# ascii.net
KiCad netlist of a schematic drawn in Altium Designer
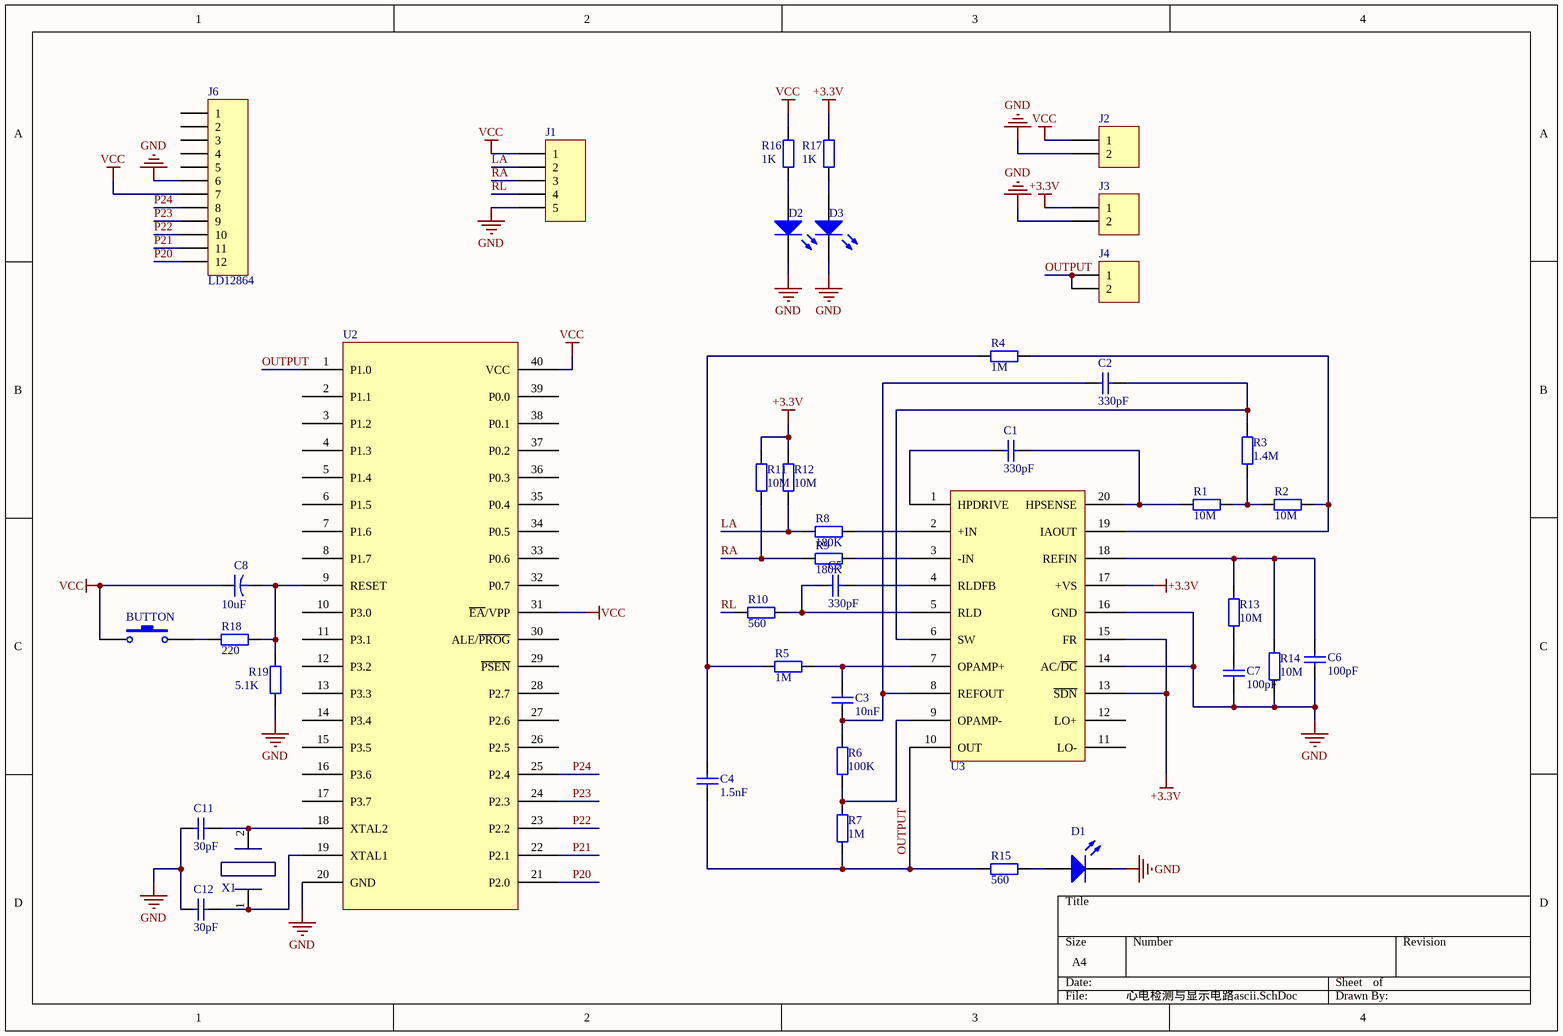
[diagram p0: 心电检测与显示电路ascii.SchDoc]

(export (version "E")
  (design (tool "Eeschema 10.0.6"))
  (components
    (comp (ref "BUTTON")
      (value "SW-PB")
      (footprint "SPST-2")
      (description "Switch")
      (fields (field (name "PUBLISHER") "Altium Limited"))
      (libsource (lib "Miscellaneous Devices") (part "SW-PB"))
    )
    (comp (ref "C1")
      (value "330pF")
      (footprint "RAD-0.3")
      (description "Capacitor")
      (fields (field (name "Comment") "Cap") (field (name "PUBLISHER") "Altium Limited"))
      (libsource (lib "Miscellaneous Devices") (part "Cap"))
    )
    (comp (ref "C2")
      (value "330pF")
      (footprint "RAD-0.3")
      (description "Capacitor")
      (fields (field (name "Comment") "Cap") (field (name "PUBLISHER") "Altium Limited"))
      (libsource (lib "Miscellaneous Devices") (part "Cap"))
    )
    (comp (ref "C3")
      (value "10nF")
      (footprint "RAD-0.3")
      (description "Capacitor")
      (fields (field (name "Comment") "Cap") (field (name "PUBLISHER") "Altium Limited"))
      (libsource (lib "Miscellaneous Devices") (part "Cap"))
    )
    (comp (ref "C4")
      (value "1.5nF")
      (footprint "RAD-0.3")
      (description "Capacitor")
      (fields (field (name "Comment") "Cap") (field (name "PUBLISHER") "Altium Limited"))
      (libsource (lib "Miscellaneous Devices") (part "Cap"))
    )
    (comp (ref "C5")
      (value "330pF")
      (footprint "RAD-0.3")
      (description "Capacitor")
      (fields (field (name "Comment") "Cap") (field (name "PUBLISHER") "Altium Limited"))
      (libsource (lib "Miscellaneous Devices") (part "Cap"))
    )
    (comp (ref "C6")
      (value "100pF")
      (footprint "RAD-0.3")
      (description "Capacitor")
      (fields (field (name "Comment") "Cap") (field (name "PUBLISHER") "Altium Limited"))
      (libsource (lib "Miscellaneous Devices") (part "Cap"))
    )
    (comp (ref "C7")
      (value "100pF")
      (footprint "RAD-0.3")
      (description "Capacitor")
      (fields (field (name "Comment") "Cap") (field (name "PUBLISHER") "Altium Limited"))
      (libsource (lib "Miscellaneous Devices") (part "Cap"))
    )
    (comp (ref "C8")
      (value "10uF")
      (footprint "CAPR5-4X5")
      (description "Capacitor")
      (fields (field (name "Comment") "Cap2") (field (name "PUBLISHER") "Altium Limited"))
      (libsource (lib "Miscellaneous Devices") (part "Cap2"))
    )
    (comp (ref "C11")
      (value "30pF")
      (footprint "RAD-0.3")
      (description "Capacitor")
      (fields (field (name "Comment") "Cap") (field (name "PUBLISHER") "Altium Limited"))
      (libsource (lib "Miscellaneous Devices") (part "Cap"))
    )
    (comp (ref "C12")
      (value "30pF")
      (footprint "RAD-0.3")
      (description "Capacitor")
      (fields (field (name "Comment") "Cap") (field (name "PUBLISHER") "Altium Limited"))
      (libsource (lib "Miscellaneous Devices") (part "Cap"))
    )
    (comp (ref "D1")
      (value "LED1")
      (footprint "LED-1")
      (description "Typical RED GaAs LED")
      (fields (field (name "PUBLISHER") "Altium Limited"))
      (libsource (lib "Miscellaneous Devices") (part "LED1"))
    )
    (comp (ref "D2")
      (value "LED1")
      (footprint "LED-1")
      (description "Typical RED GaAs LED")
      (fields (field (name "PUBLISHER") "Altium Limited"))
      (libsource (lib "Miscellaneous Devices") (part "LED1"))
    )
    (comp (ref "D3")
      (value "LED1")
      (footprint "LED-1")
      (description "Typical RED GaAs LED")
      (fields (field (name "PUBLISHER") "Altium Limited"))
      (libsource (lib "Miscellaneous Devices") (part "LED1"))
    )
    (comp (ref "J1")
      (value "MICROUSB")
      (footprint "HDR1X5")
      (description "Header, 5-Pin")
      (fields (field (name "PUBLISHER") "Altium Limited"))
      (libsource (lib "Miscellaneous Connectors") (part "Header 5"))
    )
    (comp (ref "J2")
      (value "Header 2")
      (footprint "HDR1X2")
      (description "Header, 2-Pin")
      (fields (field (name "PUBLISHER") "Altium Limited"))
      (libsource (lib "Miscellaneous Connectors") (part "Header 2"))
    )
    (comp (ref "J3")
      (value "Header 2")
      (footprint "HDR1X2")
      (description "Header, 2-Pin")
      (fields (field (name "PUBLISHER") "Altium Limited"))
      (libsource (lib "Miscellaneous Connectors") (part "Header 2"))
    )
    (comp (ref "J4")
      (value "Header 2")
      (footprint "HDR1X2")
      (description "Header, 2-Pin")
      (fields (field (name "PUBLISHER") "Altium Limited"))
      (libsource (lib "Miscellaneous Connectors") (part "Header 2"))
    )
    (comp (ref "J6")
      (value "LD12864")
      (footprint "HDR1X12")
      (description "Header, 12-Pin")
      (fields (field (name "PUBLISHER") "Altium Limited"))
      (libsource (lib "Miscellaneous Connectors") (part "Header 12"))
    )
    (comp (ref "R1")
      (value "10M")
      (footprint "AXIAL-0.4")
      (description "Resistor")
      (fields (field (name "Comment") "Res2") (field (name "PUBLISHER") "Altium Limited"))
      (libsource (lib "Miscellaneous Devices") (part "Res2"))
    )
    (comp (ref "R2")
      (value "10M")
      (footprint "AXIAL-0.4")
      (description "Resistor")
      (fields (field (name "Comment") "Res2") (field (name "PUBLISHER") "Altium Limited"))
      (libsource (lib "Miscellaneous Devices") (part "Res2"))
    )
    (comp (ref "R3")
      (value "1.4M")
      (footprint "AXIAL-0.4")
      (description "Resistor")
      (fields (field (name "Comment") "Res2") (field (name "PUBLISHER") "Altium Limited"))
      (libsource (lib "") (part "Res2_1"))
    )
    (comp (ref "R4")
      (value "1M")
      (footprint "AXIAL-0.4")
      (description "Resistor")
      (fields (field (name "Comment") "Res2") (field (name "PUBLISHER") "Altium Limited"))
      (libsource (lib "") (part "Res2_2"))
    )
    (comp (ref "R5")
      (value "1M")
      (footprint "AXIAL-0.4")
      (description "Resistor")
      (fields (field (name "Comment") "Res2") (field (name "PUBLISHER") "Altium Limited"))
      (libsource (lib "") (part "Res2_2"))
    )
    (comp (ref "R6")
      (value "100K")
      (footprint "AXIAL-0.4")
      (description "Resistor")
      (fields (field (name "Comment") "Res2") (field (name "PUBLISHER") "Altium Limited"))
      (libsource (lib "") (part "Res2_3"))
    )
    (comp (ref "R7")
      (value "1M")
      (footprint "AXIAL-0.4")
      (description "Resistor")
      (fields (field (name "Comment") "Res2") (field (name "PUBLISHER") "Altium Limited"))
      (libsource (lib "") (part "Res2_3"))
    )
    (comp (ref "R8")
      (value "180K")
      (footprint "AXIAL-0.4")
      (description "Resistor")
      (fields (field (name "Comment") "Res2") (field (name "PUBLISHER") "Altium Limited"))
      (libsource (lib "") (part "Res2_2"))
    )
    (comp (ref "R9")
      (value "180K")
      (footprint "AXIAL-0.4")
      (description "Resistor")
      (fields (field (name "Comment") "Res2") (field (name "PUBLISHER") "Altium Limited"))
      (libsource (lib "") (part "Res2_2"))
    )
    (comp (ref "R10")
      (value "560")
      (footprint "AXIAL-0.4")
      (description "Resistor")
      (fields (field (name "Comment") "Res2") (field (name "PUBLISHER") "Altium Limited"))
      (libsource (lib "") (part "Res2_2"))
    )
    (comp (ref "R11")
      (value "10M")
      (footprint "AXIAL-0.4")
      (description "Resistor")
      (fields (field (name "Comment") "Res2") (field (name "PUBLISHER") "Altium Limited"))
      (libsource (lib "") (part "Res2_3"))
    )
    (comp (ref "R12")
      (value "10M")
      (footprint "AXIAL-0.4")
      (description "Resistor")
      (fields (field (name "Comment") "Res2") (field (name "PUBLISHER") "Altium Limited"))
      (libsource (lib "") (part "Res2_3"))
    )
    (comp (ref "R13")
      (value "10M")
      (footprint "AXIAL-0.4")
      (description "Resistor")
      (fields (field (name "Comment") "Res2") (field (name "PUBLISHER") "Altium Limited"))
      (libsource (lib "") (part "Res2_3"))
    )
    (comp (ref "R14")
      (value "10M")
      (footprint "AXIAL-0.4")
      (description "Resistor")
      (fields (field (name "Comment") "Res2") (field (name "PUBLISHER") "Altium Limited"))
      (libsource (lib "") (part "Res2_3"))
    )
    (comp (ref "R15")
      (value "560")
      (footprint "AXIAL-0.4")
      (description "Resistor")
      (fields (field (name "Comment") "Res2") (field (name "PUBLISHER") "Altium Limited"))
      (libsource (lib "") (part "Res2_2"))
    )
    (comp (ref "R16")
      (value "1K")
      (footprint "AXIAL-0.4")
      (description "Resistor")
      (fields (field (name "Comment") "Res2") (field (name "PUBLISHER") "Altium Limited"))
      (libsource (lib "") (part "Res2_1"))
    )
    (comp (ref "R17")
      (value "1K")
      (footprint "AXIAL-0.4")
      (description "Resistor")
      (fields (field (name "Comment") "Res2") (field (name "PUBLISHER") "Altium Limited"))
      (libsource (lib "") (part "Res2_1"))
    )
    (comp (ref "R18")
      (value "220")
      (footprint "AXIAL-0.4")
      (description "Resistor")
      (fields (field (name "Comment") "Res2") (field (name "PUBLISHER") "Altium Limited"))
      (libsource (lib "Miscellaneous Devices") (part "Res2"))
    )
    (comp (ref "R19")
      (value "5.1K")
      (footprint "AXIAL-0.4")
      (description "Resistor")
      (fields (field (name "Comment") "Res2") (field (name "PUBLISHER") "Altium Limited"))
      (libsource (lib "") (part "Res2_1"))
    )
    (comp (ref "U2") (value "89c51") (footprint "89c51") (libsource (lib "89c51") (part "Component_1")))
    (comp (ref "U3")
      (value "Component_1")
      (footprint "AD8232")
      (libsource (lib "AD8232") (part "Component_1"))
    )
    (comp (ref "X1")
      (value "Component_1")
      (footprint "LC-HC-49S")
      (libsource (lib "晶振") (part "Component_1"))
    )
  )
  (nets
    (net (code "1") (name "+3.3V") (class "Default")
      (node (ref "J3") (pin "1") (pinfunction "1_1") (pintype "passive"))
      (node (ref "R11") (pin "1") (pinfunction "1_1") (pintype "passive"))
      (node (ref "R12") (pin "1") (pinfunction "1_1") (pintype "passive"))
      (node (ref "R17") (pin "2") (pinfunction "2_2") (pintype "passive"))
      (node (ref "U3") (pin "13") (pinfunction "~{SDN}_13") (pintype "passive"))
      (node (ref "U3") (pin "15") (pinfunction "FR_15") (pintype "passive"))
      (node (ref "U3") (pin "17") (pinfunction "+VS_17") (pintype "passive"))
    )
    (net (code "2") (name "/LA") (class "Default")
      (node (ref "J1") (pin "2") (pinfunction "2_2") (pintype "passive"))
      (node (ref "R12") (pin "2") (pinfunction "2_2") (pintype "passive"))
      (node (ref "R8") (pin "2") (pinfunction "2_2") (pintype "passive"))
    )
    (net (code "3") (name "/OUTPUT") (class "Default")
      (node (ref "C4") (pin "1") (pinfunction "1_1") (pintype "passive"))
      (node (ref "J4") (pin "1") (pinfunction "1_1") (pintype "passive"))
      (node (ref "J4") (pin "2") (pinfunction "2_2") (pintype "passive"))
      (node (ref "R15") (pin "2") (pinfunction "2_2") (pintype "passive"))
      (node (ref "R7") (pin "2") (pinfunction "2_2") (pintype "passive"))
      (node (ref "U2") (pin "1") (pinfunction "P1.0_1") (pintype "passive"))
      (node (ref "U3") (pin "10") (pinfunction "OUT_10") (pintype "passive"))
    )
    (net (code "4") (name "/P20") (class "Default")
      (node (ref "J6") (pin "12") (pinfunction "12_12") (pintype "passive"))
      (node (ref "U2") (pin "21") (pinfunction "P2.0_21") (pintype "passive"))
    )
    (net (code "5") (name "/P21") (class "Default")
      (node (ref "J6") (pin "11") (pinfunction "11_11") (pintype "passive"))
      (node (ref "U2") (pin "22") (pinfunction "P2.1_22") (pintype "passive"))
    )
    (net (code "6") (name "/P22") (class "Default")
      (node (ref "J6") (pin "10") (pinfunction "10_10") (pintype "passive"))
      (node (ref "U2") (pin "23") (pinfunction "P2.2_23") (pintype "passive"))
    )
    (net (code "7") (name "/P23") (class "Default")
      (node (ref "J6") (pin "9") (pinfunction "9_9") (pintype "passive"))
      (node (ref "U2") (pin "24") (pinfunction "P2.3_24") (pintype "passive"))
    )
    (net (code "8") (name "/P24") (class "Default")
      (node (ref "J6") (pin "8") (pinfunction "8_8") (pintype "passive"))
      (node (ref "U2") (pin "25") (pinfunction "P2.4_25") (pintype "passive"))
    )
    (net (code "9") (name "/RA") (class "Default")
      (node (ref "J1") (pin "3") (pinfunction "3_3") (pintype "passive"))
      (node (ref "R11") (pin "2") (pinfunction "2_2") (pintype "passive"))
      (node (ref "R9") (pin "2") (pinfunction "2_2") (pintype "passive"))
    )
    (net (code "10") (name "/RL") (class "Default")
      (node (ref "J1") (pin "4") (pinfunction "4_4") (pintype "passive"))
      (node (ref "R10") (pin "2") (pinfunction "2_2") (pintype "passive"))
    )
    (net (code "11") (name "GND") (class "Default")
      (node (ref "C11") (pin "1") (pinfunction "1_1") (pintype "passive"))
      (node (ref "C12") (pin "1") (pinfunction "1_1") (pintype "passive"))
      (node (ref "C6") (pin "1") (pinfunction "1_1") (pintype "passive"))
      (node (ref "C7") (pin "1") (pinfunction "1_1") (pintype "passive"))
      (node (ref "D1") (pin "2") (pinfunction "K_2") (pintype "passive"))
      (node (ref "D2") (pin "2") (pinfunction "K_2") (pintype "passive"))
      (node (ref "D3") (pin "2") (pinfunction "K_2") (pintype "passive"))
      (node (ref "J1") (pin "5") (pinfunction "5_5") (pintype "passive"))
      (node (ref "J2") (pin "2") (pinfunction "2_2") (pintype "passive"))
      (node (ref "J3") (pin "2") (pinfunction "2_2") (pintype "passive"))
      (node (ref "J6") (pin "6") (pinfunction "6_6") (pintype "passive"))
      (node (ref "R14") (pin "2") (pinfunction "2_2") (pintype "passive"))
      (node (ref "R19") (pin "1") (pinfunction "1_1") (pintype "passive"))
      (node (ref "U2") (pin "20") (pinfunction "GND_20") (pintype "passive"))
      (node (ref "U3") (pin "14") (pinfunction "AC/~{DC}_14") (pintype "passive"))
      (node (ref "U3") (pin "16") (pinfunction "GND_16") (pintype "passive"))
    )
    (net (code "12") (name "Net-(BUTTON-Pad2)") (class "Default")
      (node (ref "BUTTON") (pin "2") (pinfunction "2_2") (pintype "passive"))
      (node (ref "R18") (pin "1") (pinfunction "1_1") (pintype "passive"))
    )
    (net (code "13") (name "Net-(C4-Pad2)") (class "Default")
      (node (ref "C4") (pin "2") (pinfunction "2_2") (pintype "passive"))
      (node (ref "R4") (pin "2") (pinfunction "2_2") (pintype "passive"))
      (node (ref "R5") (pin "2") (pinfunction "2_2") (pintype "passive"))
    )
    (net (code "14") (name "Net-(C7-Pad2)") (class "Default")
      (node (ref "C7") (pin "2") (pinfunction "2_2") (pintype "passive"))
      (node (ref "R13") (pin "2") (pinfunction "2_2") (pintype "passive"))
    )
    (net (code "15") (name "Net-(D1-A)") (class "Default")
      (node (ref "D1") (pin "1") (pinfunction "A_1") (pintype "passive"))
      (node (ref "R15") (pin "1") (pinfunction "1_1") (pintype "passive"))
    )
    (net (code "16") (name "Net-(D2-A)") (class "Default")
      (node (ref "D2") (pin "1") (pinfunction "A_1") (pintype "passive"))
      (node (ref "R16") (pin "1") (pinfunction "1_1") (pintype "passive"))
    )
    (net (code "17") (name "Net-(D3-A)") (class "Default")
      (node (ref "D3") (pin "1") (pinfunction "A_1") (pintype "passive"))
      (node (ref "R17") (pin "1") (pinfunction "1_1") (pintype "passive"))
    )
    (net (code "18") (name "Net-(R1-Pad2)") (class "Default")
      (node (ref "R1") (pin "2") (pinfunction "2_2") (pintype "passive"))
      (node (ref "R2") (pin "1") (pinfunction "1_1") (pintype "passive"))
      (node (ref "R3") (pin "1") (pinfunction "1_1") (pintype "passive"))
    )
    (net (code "19") (name "Net-(U2-RESET)") (class "Default")
      (node (ref "C8") (pin "2") (pinfunction "2_2") (pintype "passive"))
      (node (ref "R18") (pin "2") (pinfunction "2_2") (pintype "passive"))
      (node (ref "R19") (pin "2") (pinfunction "2_2") (pintype "passive"))
      (node (ref "U2") (pin "9") (pinfunction "RESET_9") (pintype "passive"))
    )
    (net (code "20") (name "Net-(U2-XTAL1)") (class "Default")
      (node (ref "C12") (pin "2") (pinfunction "2_2") (pintype "passive"))
      (node (ref "U2") (pin "19") (pinfunction "XTAL1_19") (pintype "passive"))
      (node (ref "X1") (pin "1") (pinfunction "1_1") (pintype "passive"))
    )
    (net (code "21") (name "Net-(U2-XTAL2)") (class "Default")
      (node (ref "C11") (pin "2") (pinfunction "2_2") (pintype "passive"))
      (node (ref "U2") (pin "18") (pinfunction "XTAL2_18") (pintype "passive"))
      (node (ref "X1") (pin "2") (pinfunction "2_2") (pintype "passive"))
    )
    (net (code "22") (name "Net-(U3-+IN)") (class "Default")
      (node (ref "R8") (pin "1") (pinfunction "1_1") (pintype "passive"))
      (node (ref "U3") (pin "2") (pinfunction "+IN_2") (pintype "passive"))
    )
    (net (code "23") (name "Net-(U3--IN)") (class "Default")
      (node (ref "R9") (pin "1") (pinfunction "1_1") (pintype "passive"))
      (node (ref "U3") (pin "3") (pinfunction "-IN_3") (pintype "passive"))
    )
    (net (code "24") (name "Net-(U3-HPDRIVE)") (class "Default")
      (node (ref "C1") (pin "1") (pinfunction "1_1") (pintype "passive"))
      (node (ref "U3") (pin "1") (pinfunction "HPDRIVE_1") (pintype "passive"))
    )
    (net (code "25") (name "Net-(U3-HPSENSE)") (class "Default")
      (node (ref "C1") (pin "2") (pinfunction "2_2") (pintype "passive"))
      (node (ref "R1") (pin "1") (pinfunction "1_1") (pintype "passive"))
      (node (ref "U3") (pin "20") (pinfunction "HPSENSE_20") (pintype "passive"))
    )
    (net (code "26") (name "Net-(U3-IAOUT)") (class "Default")
      (node (ref "R2") (pin "2") (pinfunction "2_2") (pintype "passive"))
      (node (ref "R4") (pin "1") (pinfunction "1_1") (pintype "passive"))
      (node (ref "U3") (pin "19") (pinfunction "IAOUT_19") (pintype "passive"))
    )
    (net (code "27") (name "Net-(U3-OPAMP+)") (class "Default")
      (node (ref "C3") (pin "2") (pinfunction "2_2") (pintype "passive"))
      (node (ref "R5") (pin "1") (pinfunction "1_1") (pintype "passive"))
      (node (ref "U3") (pin "7") (pinfunction "OPAMP+_7") (pintype "passive"))
    )
    (net (code "28") (name "Net-(U3-OPAMP-)") (class "Default")
      (node (ref "R6") (pin "2") (pinfunction "2_2") (pintype "passive"))
      (node (ref "R7") (pin "1") (pinfunction "1_1") (pintype "passive"))
      (node (ref "U3") (pin "9") (pinfunction "OPAMP-_9") (pintype "passive"))
    )
    (net (code "29") (name "Net-(U3-REFIN)") (class "Default")
      (node (ref "C6") (pin "2") (pinfunction "2_2") (pintype "passive"))
      (node (ref "R13") (pin "1") (pinfunction "1_1") (pintype "passive"))
      (node (ref "R14") (pin "1") (pinfunction "1_1") (pintype "passive"))
      (node (ref "U3") (pin "18") (pinfunction "REFIN_18") (pintype "passive"))
    )
    (net (code "30") (name "Net-(U3-REFOUT)") (class "Default")
      (node (ref "C2") (pin "1") (pinfunction "1_1") (pintype "passive"))
      (node (ref "C3") (pin "1") (pinfunction "1_1") (pintype "passive"))
      (node (ref "R6") (pin "1") (pinfunction "1_1") (pintype "passive"))
      (node (ref "U3") (pin "8") (pinfunction "REFOUT_8") (pintype "passive"))
    )
    (net (code "31") (name "Net-(U3-RLD)") (class "Default")
      (node (ref "C5") (pin "1") (pinfunction "1_1") (pintype "passive"))
      (node (ref "R10") (pin "1") (pinfunction "1_1") (pintype "passive"))
      (node (ref "U3") (pin "5") (pinfunction "RLD_5") (pintype "passive"))
    )
    (net (code "32") (name "Net-(U3-RLDFB)") (class "Default")
      (node (ref "C5") (pin "2") (pinfunction "2_2") (pintype "passive"))
      (node (ref "U3") (pin "4") (pinfunction "RLDFB_4") (pintype "passive"))
    )
    (net (code "33") (name "Net-(U3-SW)") (class "Default")
      (node (ref "C2") (pin "2") (pinfunction "2_2") (pintype "passive"))
      (node (ref "R3") (pin "2") (pinfunction "2_2") (pintype "passive"))
      (node (ref "U3") (pin "6") (pinfunction "SW_6") (pintype "passive"))
    )
    (net (code "34") (name "VCC") (class "Default")
      (node (ref "BUTTON") (pin "1") (pinfunction "1_1") (pintype "passive"))
      (node (ref "C8") (pin "1") (pinfunction "1_1") (pintype "passive"))
      (node (ref "J1") (pin "1") (pinfunction "1_1") (pintype "passive"))
      (node (ref "J2") (pin "1") (pinfunction "1_1") (pintype "passive"))
      (node (ref "J6") (pin "7") (pinfunction "7_7") (pintype "passive"))
      (node (ref "R16") (pin "2") (pinfunction "2_2") (pintype "passive"))
      (node (ref "U2") (pin "31") (pinfunction "~{EA}/VPP_31") (pintype "passive"))
      (node (ref "U2") (pin "40") (pinfunction "VCC_40") (pintype "passive"))
    )
    (net (code "35") (name "unconnected-(J6-Pad1)") (class "Default")
      (node (ref "J6") (pin "1") (pinfunction "1_1") (pintype "passive"))
    )
    (net (code "36") (name "unconnected-(J6-Pad2)") (class "Default")
      (node (ref "J6") (pin "2") (pinfunction "2_2") (pintype "passive"))
    )
    (net (code "37") (name "unconnected-(J6-Pad3)") (class "Default")
      (node (ref "J6") (pin "3") (pinfunction "3_3") (pintype "passive"))
    )
    (net (code "38") (name "unconnected-(J6-Pad4)") (class "Default")
      (node (ref "J6") (pin "4") (pinfunction "4_4") (pintype "passive"))
    )
    (net (code "39") (name "unconnected-(J6-Pad5)") (class "Default")
      (node (ref "J6") (pin "5") (pinfunction "5_5") (pintype "passive"))
    )
    (net (code "40") (name "unconnected-(U2-ALE{slash}~{PROG}-Pad30)") (class "Default")
      (node (ref "U2") (pin "30") (pinfunction "ALE/~{PROG}_30") (pintype "passive"))
    )
    (net (code "41") (name "unconnected-(U2-P0.0-Pad39)") (class "Default")
      (node (ref "U2") (pin "39") (pinfunction "P0.0_39") (pintype "passive"))
    )
    (net (code "42") (name "unconnected-(U2-P0.1-Pad38)") (class "Default")
      (node (ref "U2") (pin "38") (pinfunction "P0.1_38") (pintype "passive"))
    )
    (net (code "43") (name "unconnected-(U2-P0.2-Pad37)") (class "Default")
      (node (ref "U2") (pin "37") (pinfunction "P0.2_37") (pintype "passive"))
    )
    (net (code "44") (name "unconnected-(U2-P0.3-Pad36)") (class "Default")
      (node (ref "U2") (pin "36") (pinfunction "P0.3_36") (pintype "passive"))
    )
    (net (code "45") (name "unconnected-(U2-P0.4-Pad35)") (class "Default")
      (node (ref "U2") (pin "35") (pinfunction "P0.4_35") (pintype "passive"))
    )
    (net (code "46") (name "unconnected-(U2-P0.5-Pad34)") (class "Default")
      (node (ref "U2") (pin "34") (pinfunction "P0.5_34") (pintype "passive"))
    )
    (net (code "47") (name "unconnected-(U2-P0.6-Pad33)") (class "Default")
      (node (ref "U2") (pin "33") (pinfunction "P0.6_33") (pintype "passive"))
    )
    (net (code "48") (name "unconnected-(U2-P0.7-Pad32)") (class "Default")
      (node (ref "U2") (pin "32") (pinfunction "P0.7_32") (pintype "passive"))
    )
    (net (code "49") (name "unconnected-(U2-P1.1-Pad2)") (class "Default")
      (node (ref "U2") (pin "2") (pinfunction "P1.1_2") (pintype "passive"))
    )
    (net (code "50") (name "unconnected-(U2-P1.2-Pad3)") (class "Default")
      (node (ref "U2") (pin "3") (pinfunction "P1.2_3") (pintype "passive"))
    )
    (net (code "51") (name "unconnected-(U2-P1.3-Pad4)") (class "Default")
      (node (ref "U2") (pin "4") (pinfunction "P1.3_4") (pintype "passive"))
    )
    (net (code "52") (name "unconnected-(U2-P1.4-Pad5)") (class "Default")
      (node (ref "U2") (pin "5") (pinfunction "P1.4_5") (pintype "passive"))
    )
    (net (code "53") (name "unconnected-(U2-P1.5-Pad6)") (class "Default")
      (node (ref "U2") (pin "6") (pinfunction "P1.5_6") (pintype "passive"))
    )
    (net (code "54") (name "unconnected-(U2-P1.6-Pad7)") (class "Default")
      (node (ref "U2") (pin "7") (pinfunction "P1.6_7") (pintype "passive"))
    )
    (net (code "55") (name "unconnected-(U2-P1.7-Pad8)") (class "Default")
      (node (ref "U2") (pin "8") (pinfunction "P1.7_8") (pintype "passive"))
    )
    (net (code "56") (name "unconnected-(U2-P2.5-Pad26)") (class "Default")
      (node (ref "U2") (pin "26") (pinfunction "P2.5_26") (pintype "passive"))
    )
    (net (code "57") (name "unconnected-(U2-P2.6-Pad27)") (class "Default")
      (node (ref "U2") (pin "27") (pinfunction "P2.6_27") (pintype "passive"))
    )
    (net (code "58") (name "unconnected-(U2-P2.7-Pad28)") (class "Default")
      (node (ref "U2") (pin "28") (pinfunction "P2.7_28") (pintype "passive"))
    )
    (net (code "59") (name "unconnected-(U2-P3.0-Pad10)") (class "Default")
      (node (ref "U2") (pin "10") (pinfunction "P3.0_10") (pintype "passive"))
    )
    (net (code "60") (name "unconnected-(U2-P3.1-Pad11)") (class "Default")
      (node (ref "U2") (pin "11") (pinfunction "P3.1_11") (pintype "passive"))
    )
    (net (code "61") (name "unconnected-(U2-P3.2-Pad12)") (class "Default")
      (node (ref "U2") (pin "12") (pinfunction "P3.2_12") (pintype "passive"))
    )
    (net (code "62") (name "unconnected-(U2-P3.3-Pad13)") (class "Default")
      (node (ref "U2") (pin "13") (pinfunction "P3.3_13") (pintype "passive"))
    )
    (net (code "63") (name "unconnected-(U2-P3.4-Pad14)") (class "Default")
      (node (ref "U2") (pin "14") (pinfunction "P3.4_14") (pintype "passive"))
    )
    (net (code "64") (name "unconnected-(U2-P3.5-Pad15)") (class "Default")
      (node (ref "U2") (pin "15") (pinfunction "P3.5_15") (pintype "passive"))
    )
    (net (code "65") (name "unconnected-(U2-P3.6-Pad16)") (class "Default")
      (node (ref "U2") (pin "16") (pinfunction "P3.6_16") (pintype "passive"))
    )
    (net (code "66") (name "unconnected-(U2-P3.7-Pad17)") (class "Default")
      (node (ref "U2") (pin "17") (pinfunction "P3.7_17") (pintype "passive"))
    )
    (net (code "67") (name "unconnected-(U2-~{PSEN}-Pad29)") (class "Default")
      (node (ref "U2") (pin "29") (pinfunction "~{PSEN}_29") (pintype "passive"))
    )
    (net (code "68") (name "unconnected-(U3-LO+-Pad12)") (class "Default")
      (node (ref "U3") (pin "12") (pinfunction "LO+_12") (pintype "passive"))
    )
    (net (code "69") (name "unconnected-(U3-LO--Pad11)") (class "Default")
      (node (ref "U3") (pin "11") (pinfunction "LO-_11") (pintype "passive"))
    )
  )
)
